# RP2040_MCU.net
KiCad netlist of a schematic drawn in Altium Designer
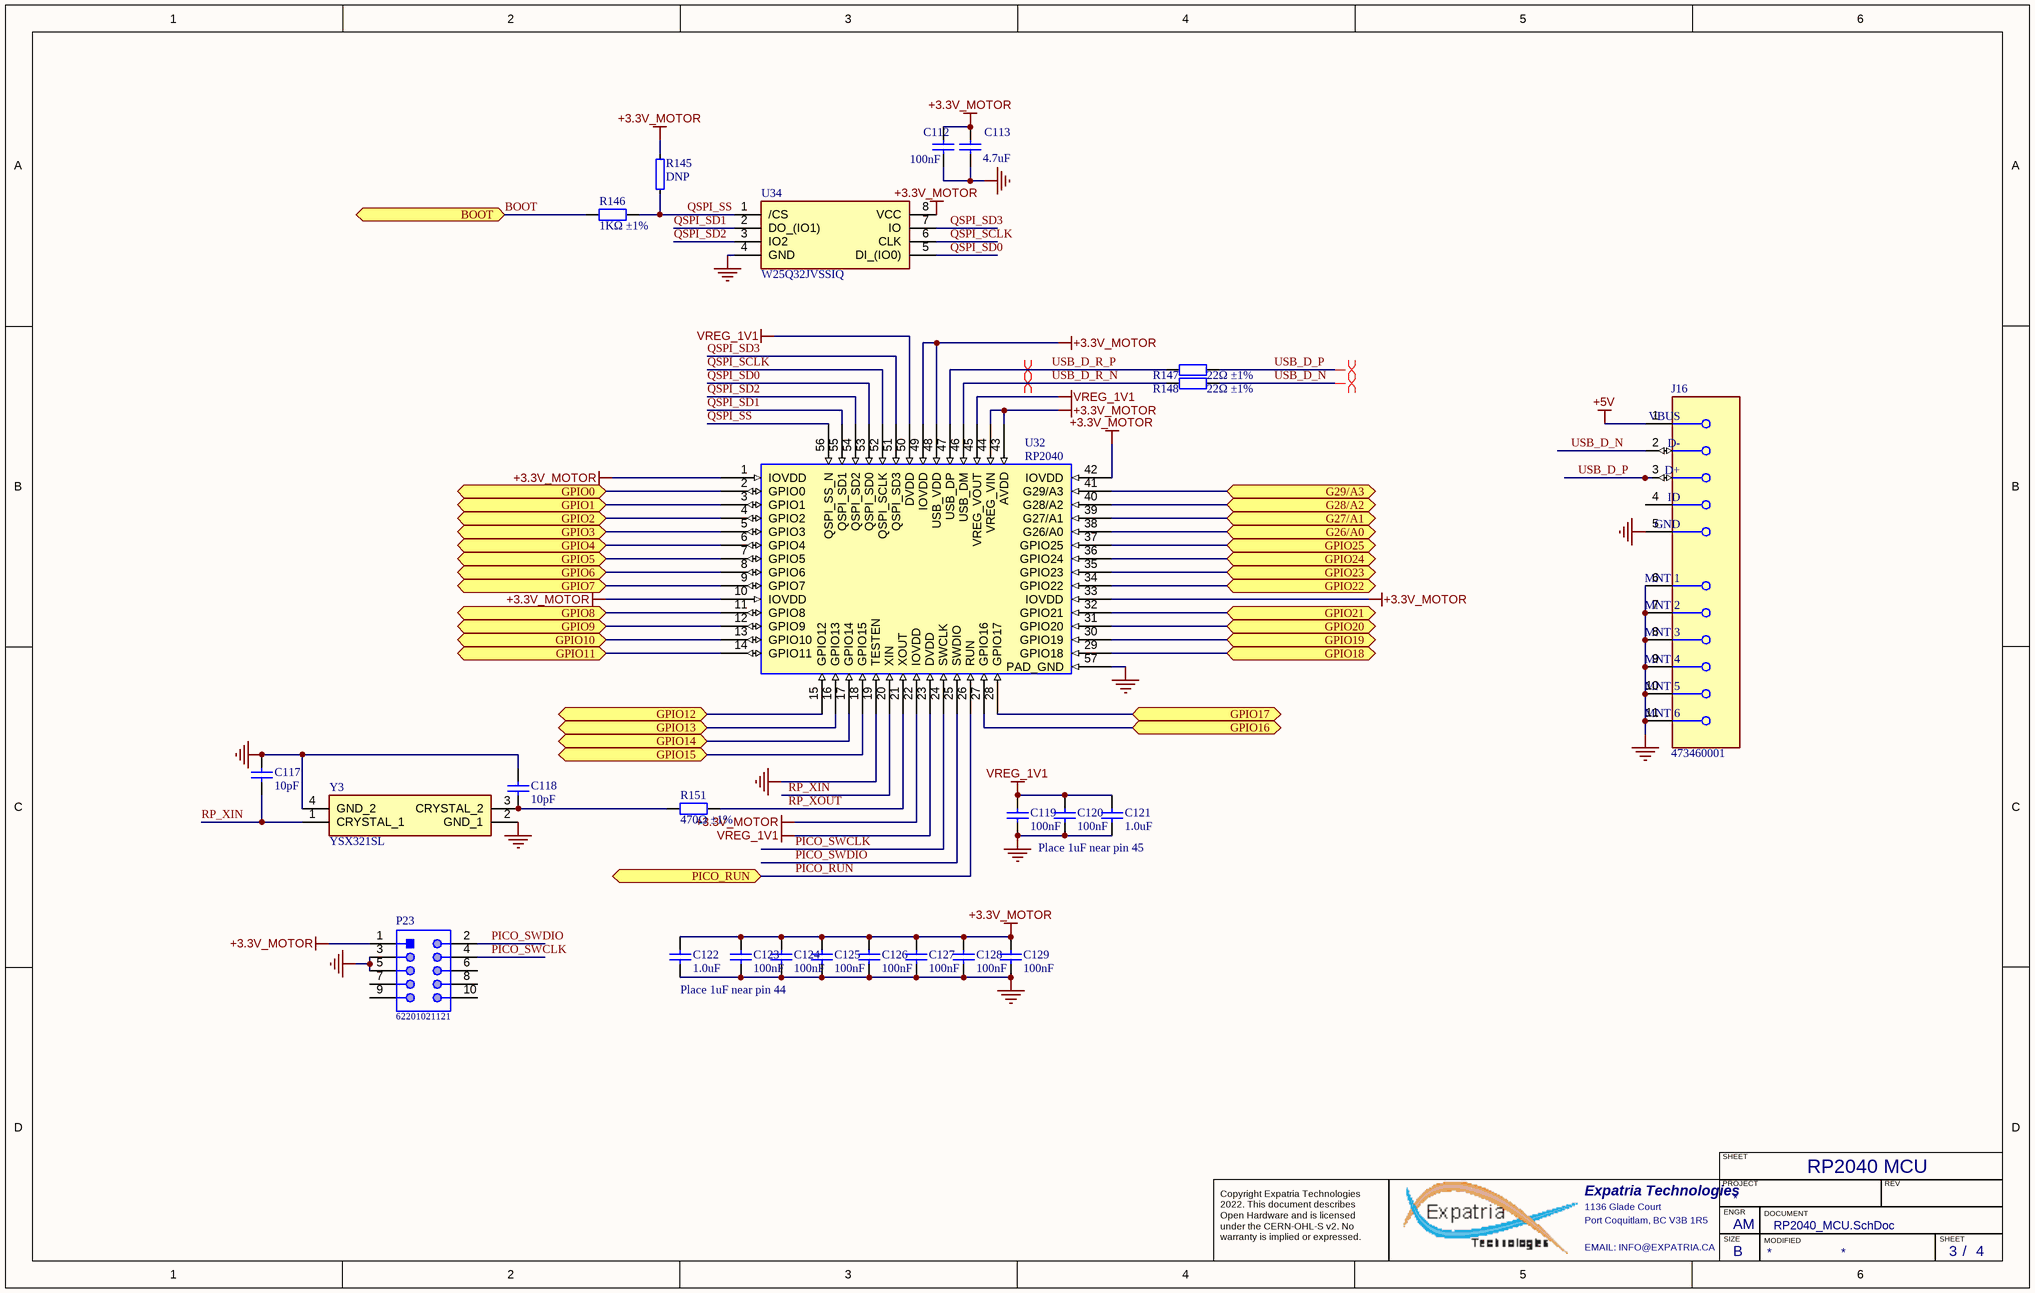
[diagram p0: RP2040_MCU.SchDoc]

(export (version "E")
  (design (tool "Eeschema 10.0.6"))
  (components
    (comp (ref "C112")
      (value "100nF")
      (footprint "0402_C")
      (description "Chip capacitors")
      (fields
        (field (name "MANUFACTURER") "Samsung Electro-Mechanics")
        (field (name "PARTNUMBER") "CL05B104KO5NNNC")
      )
      (libsource (lib "Cap") (part "0402 100nF (104) 10% 16V"))
    )
    (comp (ref "C113")
      (value "4.7uF")
      (footprint "0402_C")
      (description "Chip capacitor")
      (fields
        (field (name "MANUFACTURER") "Samsung Electro-Mechanics")
        (field (name "PARTNUMBER") "CL05A475MP5NRNC")
      )
      (libsource (lib "Cap") (part "0402 4.7uF (475) 20% 10V"))
    )
    (comp (ref "C117")
      (value "10pF")
      (footprint "0402_C")
      (description "Chip capacitors")
      (fields
        (field (name "MANUFACTURER") "Samsung Electro-Mechanics")
        (field (name "PARTNUMBER") "CL05C100JB5NNNC")
      )
      (libsource (lib "Cap") (part "0402 10pF (100) 5% 50V"))
    )
    (comp (ref "C118")
      (value "10pF")
      (footprint "0402_C")
      (description "Chip capacitors")
      (fields
        (field (name "MANUFACTURER") "Samsung Electro-Mechanics")
        (field (name "PARTNUMBER") "CL05C100JB5NNNC")
      )
      (libsource (lib "Cap") (part "0402 10pF (100) 5% 50V"))
    )
    (comp (ref "C119")
      (value "100nF")
      (footprint "0402_C")
      (description "Chip capacitors")
      (fields
        (field (name "MANUFACTURER") "Samsung Electro-Mechanics")
        (field (name "PARTNUMBER") "CL05B104KO5NNNC")
      )
      (libsource (lib "Cap") (part "0402 100nF (104) 10% 16V"))
    )
    (comp (ref "C120")
      (value "100nF")
      (footprint "0402_C")
      (description "Chip capacitors")
      (fields
        (field (name "MANUFACTURER") "Samsung Electro-Mechanics")
        (field (name "PARTNUMBER") "CL05B104KO5NNNC")
      )
      (libsource (lib "Cap") (part "0402 100nF (104) 10% 16V"))
    )
    (comp (ref "C121")
      (value "1.0uF")
      (footprint "0402_C")
      (description "Chip capacitor")
      (fields
        (field (name "MANUFACTURER") "Samsung Electro-Mechanics")
        (field (name "PARTNUMBER") "CL05A105KA5NQNC")
      )
      (libsource (lib "Cap") (part "0402 1.0uF (105) 10% 25V"))
    )
    (comp (ref "C122")
      (value "1.0uF")
      (footprint "0402_C")
      (description "Chip capacitor")
      (fields
        (field (name "MANUFACTURER") "Samsung Electro-Mechanics")
        (field (name "PARTNUMBER") "CL05A105KA5NQNC")
      )
      (libsource (lib "Cap") (part "0402 1.0uF (105) 10% 25V"))
    )
    (comp (ref "C123")
      (value "100nF")
      (footprint "0402_C")
      (description "Chip capacitors")
      (fields
        (field (name "MANUFACTURER") "Samsung Electro-Mechanics")
        (field (name "PARTNUMBER") "CL05B104KO5NNNC")
      )
      (libsource (lib "Cap") (part "0402 100nF (104) 10% 16V"))
    )
    (comp (ref "C124")
      (value "100nF")
      (footprint "0402_C")
      (description "Chip capacitors")
      (fields
        (field (name "MANUFACTURER") "Samsung Electro-Mechanics")
        (field (name "PARTNUMBER") "CL05B104KO5NNNC")
      )
      (libsource (lib "Cap") (part "0402 100nF (104) 10% 16V"))
    )
    (comp (ref "C125")
      (value "100nF")
      (footprint "0402_C")
      (description "Chip capacitors")
      (fields
        (field (name "MANUFACTURER") "Samsung Electro-Mechanics")
        (field (name "PARTNUMBER") "CL05B104KO5NNNC")
      )
      (libsource (lib "Cap") (part "0402 100nF (104) 10% 16V"))
    )
    (comp (ref "C126")
      (value "100nF")
      (footprint "0402_C")
      (description "Chip capacitors")
      (fields
        (field (name "MANUFACTURER") "Samsung Electro-Mechanics")
        (field (name "PARTNUMBER") "CL05B104KO5NNNC")
      )
      (libsource (lib "Cap") (part "0402 100nF (104) 10% 16V"))
    )
    (comp (ref "C127")
      (value "100nF")
      (footprint "0402_C")
      (description "Chip capacitors")
      (fields
        (field (name "MANUFACTURER") "Samsung Electro-Mechanics")
        (field (name "PARTNUMBER") "CL05B104KO5NNNC")
      )
      (libsource (lib "Cap") (part "0402 100nF (104) 10% 16V"))
    )
    (comp (ref "C128")
      (value "100nF")
      (footprint "0402_C")
      (description "Chip capacitors")
      (fields
        (field (name "MANUFACTURER") "Samsung Electro-Mechanics")
        (field (name "PARTNUMBER") "CL05B104KO5NNNC")
      )
      (libsource (lib "Cap") (part "0402 100nF (104) 10% 16V"))
    )
    (comp (ref "C129")
      (value "100nF")
      (footprint "0402_C")
      (description "Chip capacitors")
      (fields
        (field (name "MANUFACTURER") "Samsung Electro-Mechanics")
        (field (name "PARTNUMBER") "CL05B104KO5NNNC")
      )
      (libsource (lib "Cap") (part "0402 100nF (104) 10% 16V"))
    )
    (comp (ref "J16")
      (value "473460001")
      (footprint "FP-473460001-MFG")
      (description "CONN RCPT USB2.0 MICRO B SMD R/A")
      (fields
        (field (name "OCTOPART") "https://octopart.com/47346-0001-molex-7164928")
        (field (name "MANUFACTURER") "Molex")
      )
      (libsource (lib "Altium Content Vault") (part "53ae1f1d9b557310b43ca686e5bb76a"))
    )
    (comp (ref "P23")
      (value "62201021121")
      (footprint "62201021121")
      (description "THT Vertical Pin Header WR-PHD, Pitch 1.27 mm, Dual Row, 10 pins")
      (fields (field (name "MANUFACTURER") "Wurth Elektronik") (field (name "PUBLISHER") "WurthElektronik"))
      (libsource (lib "Altium Content Vault") (part "WE-CN-2P-M-R10"))
    )
    (comp (ref "R145")
      (value "DNP")
      (footprint "0402")
      (description "Resistor, ±5%, 0.05W")
      (fields (field (name "PART NUMBER") "R0201-0R") (field (name "PUBLISHER") "Nordic Semiconductor"))
      (libsource (lib "Passives") (part "RES"))
    )
    (comp (ref "R146")
      (value "1KΩ ±1%")
      (footprint "0402_R")
      (description "Chip resistor")
      (fields (field (name "MANUFACTURER") "Uniroyal Elec") (field (name "PARTNUMBER") "0402WGF1001TCE"))
      (libsource (lib "RES") (part "0402 1K (1001) 1%"))
    )
    (comp (ref "R147")
      (value "22Ω ±1%")
      (footprint "0402_R")
      (description "Chip resistor")
      (fields (field (name "MANUFACTURER") "Uniroyal Elec") (field (name "PARTNUMBER") "0402WGF220JTCE"))
      (libsource (lib "RES") (part "0402 22R (22R0) 1%"))
    )
    (comp (ref "R148")
      (value "22Ω ±1%")
      (footprint "0402_R")
      (description "Chip resistor")
      (fields (field (name "MANUFACTURER") "Uniroyal Elec") (field (name "PARTNUMBER") "0402WGF220JTCE"))
      (libsource (lib "RES") (part "0402 22R (22R0) 1%"))
    )
    (comp (ref "R151")
      (value "470Ω ±1%")
      (footprint "0402_R")
      (description "Chip resistor")
      (fields (field (name "MANUFACTURER") "Uniroyal Elec") (field (name "PARTNUMBER") "0402WGF4700TCE"))
      (libsource (lib "RES") (part "0402 470R (4700) 1%"))
    )
    (comp (ref "U32")
      (value "RP2040")
      (footprint "RP2040")
      (description "RP2040 First MCU from RPI")
      (libsource (lib "Universal_CNC_Breakout") (part "RP2040"))
    )
    (comp (ref "U34")
      (value "W25Q32JVSSIQ")
      (footprint "SamacSys:SOIC127P780X195-8N")
      (description "SPI Flash")
      (fields
        (field (name "MANUFACTURER_PART_NUMBER") "W25Q128JVSIQ TR")
        (field (name "MOUSER PART NUMBER") "454-W25Q128JVSIQTR")
      )
      (libsource (lib "*") (part "W25Q128JVSIQ_TR"))
    )
    (comp (ref "Y3")
      (value "YSX321SL")
      (footprint "SamacSys:YSX321SL")
      (description "Crystal or Oscillator")
      (libsource (lib "*") (part "YSX321SL"))
    )
  )
  (nets
    (net (code "1") (name "+3.3V_MOTOR") (class "Default")
      (node (ref "C112") (pin "2") (pinfunction "2_2") (pintype "passive"))
      (node (ref "C113") (pin "2") (pinfunction "2_2") (pintype "passive"))
      (node (ref "C122") (pin "2") (pinfunction "2_2") (pintype "passive"))
      (node (ref "C123") (pin "2") (pinfunction "2_2") (pintype "passive"))
      (node (ref "C124") (pin "2") (pinfunction "2_2") (pintype "passive"))
      (node (ref "C125") (pin "2") (pinfunction "2_2") (pintype "passive"))
      (node (ref "C126") (pin "2") (pinfunction "2_2") (pintype "passive"))
      (node (ref "C127") (pin "2") (pinfunction "2_2") (pintype "passive"))
      (node (ref "C128") (pin "2") (pinfunction "2_2") (pintype "passive"))
      (node (ref "C129") (pin "2") (pinfunction "2_2") (pintype "passive"))
      (node (ref "P23") (pin "1") (pinfunction "1_1") (pintype "passive"))
      (node (ref "R145") (pin "2") (pinfunction "2_2") (pintype "passive"))
      (node (ref "U32") (pin "1") (pinfunction "IOVDD_1") (pintype "input"))
      (node (ref "U32") (pin "10") (pinfunction "IOVDD_10") (pintype "input"))
      (node (ref "U32") (pin "22") (pinfunction "IOVDD_22") (pintype "input"))
      (node (ref "U32") (pin "33") (pinfunction "IOVDD_33") (pintype "input"))
      (node (ref "U32") (pin "42") (pinfunction "IOVDD_42") (pintype "input"))
      (node (ref "U32") (pin "43") (pinfunction "AVDD_43") (pintype "input"))
      (node (ref "U32") (pin "44") (pinfunction "VREG_VIN_44") (pintype "input"))
      (node (ref "U32") (pin "48") (pinfunction "USB_VDD_48") (pintype "input"))
      (node (ref "U32") (pin "49") (pinfunction "IOVDD_49") (pintype "input"))
      (node (ref "U34") (pin "8") (pinfunction "VCC_8") (pintype "passive"))
    )
    (net (code "2") (name "+5V") (class "Default")
      (node (ref "J16") (pin "1") (pinfunction "VBUS_1") (pintype "power_in"))
    )
    (net (code "3") (name "/BOOT") (class "Default")
      (node (ref "R146") (pin "1") (pinfunction "1_1") (pintype "passive"))
    )
    (net (code "4") (name "/G26{slash}A0") (class "Default")
      (node (ref "U32") (pin "38") (pinfunction "G26/A0_38") (pintype "input"))
    )
    (net (code "5") (name "/G27{slash}A1") (class "Default")
      (node (ref "U32") (pin "39") (pinfunction "G27/A1_39") (pintype "input"))
    )
    (net (code "6") (name "/G28{slash}A2") (class "Default")
      (node (ref "U32") (pin "40") (pinfunction "G28/A2_40") (pintype "input"))
    )
    (net (code "7") (name "/G29{slash}A3") (class "Default")
      (node (ref "U32") (pin "41") (pinfunction "G29/A3_41") (pintype "input"))
    )
    (net (code "8") (name "/GPIO0") (class "Default")
      (node (ref "U32") (pin "2") (pinfunction "GPIO0_2") (pintype "bidirectional"))
    )
    (net (code "9") (name "/GPIO1") (class "Default")
      (node (ref "U32") (pin "3") (pinfunction "GPIO1_3") (pintype "bidirectional"))
    )
    (net (code "10") (name "/GPIO2") (class "Default")
      (node (ref "U32") (pin "4") (pinfunction "GPIO2_4") (pintype "bidirectional"))
    )
    (net (code "11") (name "/GPIO3") (class "Default")
      (node (ref "U32") (pin "5") (pinfunction "GPIO3_5") (pintype "bidirectional"))
    )
    (net (code "12") (name "/GPIO4") (class "Default")
      (node (ref "U32") (pin "6") (pinfunction "GPIO4_6") (pintype "bidirectional"))
    )
    (net (code "13") (name "/GPIO5") (class "Default")
      (node (ref "U32") (pin "7") (pinfunction "GPIO5_7") (pintype "bidirectional"))
    )
    (net (code "14") (name "/GPIO6") (class "Default")
      (node (ref "U32") (pin "8") (pinfunction "GPIO6_8") (pintype "bidirectional"))
    )
    (net (code "15") (name "/GPIO7") (class "Default")
      (node (ref "U32") (pin "9") (pinfunction "GPIO7_9") (pintype "bidirectional"))
    )
    (net (code "16") (name "/GPIO8") (class "Default")
      (node (ref "U32") (pin "11") (pinfunction "GPIO8_11") (pintype "bidirectional"))
    )
    (net (code "17") (name "/GPIO9") (class "Default")
      (node (ref "U32") (pin "12") (pinfunction "GPIO9_12") (pintype "bidirectional"))
    )
    (net (code "18") (name "/GPIO10") (class "Default")
      (node (ref "U32") (pin "13") (pinfunction "GPIO10_13") (pintype "bidirectional"))
    )
    (net (code "19") (name "/GPIO11") (class "Default")
      (node (ref "U32") (pin "14") (pinfunction "GPIO11_14") (pintype "bidirectional"))
    )
    (net (code "20") (name "/GPIO12") (class "Default")
      (node (ref "U32") (pin "15") (pinfunction "GPIO12_15") (pintype "input"))
    )
    (net (code "21") (name "/GPIO13") (class "Default")
      (node (ref "U32") (pin "16") (pinfunction "GPIO13_16") (pintype "input"))
    )
    (net (code "22") (name "/GPIO14") (class "Default")
      (node (ref "U32") (pin "17") (pinfunction "GPIO14_17") (pintype "input"))
    )
    (net (code "23") (name "/GPIO15") (class "Default")
      (node (ref "U32") (pin "18") (pinfunction "GPIO15_18") (pintype "input"))
    )
    (net (code "24") (name "/GPIO16") (class "Default")
      (node (ref "U32") (pin "27") (pinfunction "GPIO16_27") (pintype "input"))
    )
    (net (code "25") (name "/GPIO17") (class "Default")
      (node (ref "U32") (pin "28") (pinfunction "GPIO17_28") (pintype "input"))
    )
    (net (code "26") (name "/GPIO18") (class "Default")
      (node (ref "U32") (pin "29") (pinfunction "GPIO18_29") (pintype "input"))
    )
    (net (code "27") (name "/GPIO19") (class "Default")
      (node (ref "U32") (pin "30") (pinfunction "GPIO19_30") (pintype "input"))
    )
    (net (code "28") (name "/GPIO20") (class "Default")
      (node (ref "U32") (pin "31") (pinfunction "GPIO20_31") (pintype "input"))
    )
    (net (code "29") (name "/GPIO21") (class "Default")
      (node (ref "U32") (pin "32") (pinfunction "GPIO21_32") (pintype "input"))
    )
    (net (code "30") (name "/GPIO22") (class "Default")
      (node (ref "U32") (pin "34") (pinfunction "GPIO22_34") (pintype "input"))
    )
    (net (code "31") (name "/GPIO23") (class "Default")
      (node (ref "U32") (pin "35") (pinfunction "GPIO23_35") (pintype "input"))
    )
    (net (code "32") (name "/GPIO24") (class "Default")
      (node (ref "U32") (pin "36") (pinfunction "GPIO24_36") (pintype "input"))
    )
    (net (code "33") (name "/GPIO25") (class "Default")
      (node (ref "U32") (pin "37") (pinfunction "GPIO25_37") (pintype "input"))
    )
    (net (code "34") (name "/PICO_RUN") (class "Default")
      (node (ref "U32") (pin "26") (pinfunction "RUN_26") (pintype "input"))
    )
    (net (code "35") (name "/PICO_SWCLK") (class "Default")
      (node (ref "P23") (pin "4") (pinfunction "4_4") (pintype "passive"))
      (node (ref "U32") (pin "24") (pinfunction "SWCLK_24") (pintype "input"))
    )
    (net (code "36") (name "/PICO_SWDIO") (class "Default")
      (node (ref "P23") (pin "2") (pinfunction "2_2") (pintype "passive"))
      (node (ref "U32") (pin "25") (pinfunction "SWDIO_25") (pintype "input"))
    )
    (net (code "37") (name "/QSPI_SCLK") (class "Default")
      (node (ref "U32") (pin "52") (pinfunction "QSPI_SCLK_52") (pintype "input"))
      (node (ref "U34") (pin "6") (pinfunction "CLK_6") (pintype "passive"))
    )
    (net (code "38") (name "/QSPI_SD0") (class "Default")
      (node (ref "U32") (pin "53") (pinfunction "QSPI_SD0_53") (pintype "input"))
      (node (ref "U34") (pin "5") (pinfunction "DI_(IO0)_5") (pintype "passive"))
    )
    (net (code "39") (name "/QSPI_SD1") (class "Default")
      (node (ref "U32") (pin "55") (pinfunction "QSPI_SD1_55") (pintype "input"))
      (node (ref "U34") (pin "2") (pinfunction "DO_(IO1)_2") (pintype "passive"))
    )
    (net (code "40") (name "/QSPI_SD2") (class "Default")
      (node (ref "U32") (pin "54") (pinfunction "QSPI_SD2_54") (pintype "input"))
      (node (ref "U34") (pin "3") (pinfunction "IO2_3") (pintype "passive"))
    )
    (net (code "41") (name "/QSPI_SD3") (class "Default")
      (node (ref "U32") (pin "51") (pinfunction "QSPI_SD3_51") (pintype "input"))
      (node (ref "U34") (pin "7") (pinfunction "IO_7") (pintype "passive"))
    )
    (net (code "42") (name "/QSPI_SS") (class "Default")
      (node (ref "R145") (pin "1") (pinfunction "1_1") (pintype "passive"))
      (node (ref "R146") (pin "2") (pinfunction "2_2") (pintype "passive"))
      (node (ref "U32") (pin "56") (pinfunction "QSPI_SS_N_56") (pintype "input"))
      (node (ref "U34") (pin "1") (pinfunction "/CS_1") (pintype "passive"))
    )
    (net (code "43") (name "/RP_XIN") (class "Default")
      (node (ref "C117") (pin "1") (pinfunction "1_1") (pintype "passive"))
      (node (ref "U32") (pin "20") (pinfunction "XIN_20") (pintype "input"))
      (node (ref "Y3") (pin "1") (pinfunction "CRYSTAL_1_1") (pintype "passive"))
    )
    (net (code "44") (name "/RP_XOUT") (class "Default")
      (node (ref "R151") (pin "2") (pinfunction "2_2") (pintype "passive"))
      (node (ref "U32") (pin "21") (pinfunction "XOUT_21") (pintype "input"))
    )
    (net (code "45") (name "/USB_D_N") (class "Default")
      (node (ref "J16") (pin "2") (pinfunction "D-_2") (pintype "bidirectional"))
      (node (ref "R148") (pin "1") (pinfunction "1_1") (pintype "passive"))
    )
    (net (code "46") (name "/USB_D_P") (class "Default")
      (node (ref "J16") (pin "3") (pinfunction "D+_3") (pintype "bidirectional"))
      (node (ref "R147") (pin "1") (pinfunction "1_1") (pintype "passive"))
    )
    (net (code "47") (name "/USB_D_R_N") (class "Default")
      (node (ref "R148") (pin "2") (pinfunction "2_2") (pintype "passive"))
      (node (ref "U32") (pin "46") (pinfunction "USB_DM_46") (pintype "input"))
    )
    (net (code "48") (name "/USB_D_R_P") (class "Default")
      (node (ref "R147") (pin "2") (pinfunction "2_2") (pintype "passive"))
      (node (ref "U32") (pin "47") (pinfunction "USB_DP_47") (pintype "input"))
    )
    (net (code "49") (name "GND") (class "Default")
      (node (ref "C112") (pin "1") (pinfunction "1_1") (pintype "passive"))
      (node (ref "C113") (pin "1") (pinfunction "1_1") (pintype "passive"))
      (node (ref "C117") (pin "2") (pinfunction "2_2") (pintype "passive"))
      (node (ref "C118") (pin "2") (pinfunction "2_2") (pintype "passive"))
      (node (ref "C119") (pin "1") (pinfunction "1_1") (pintype "passive"))
      (node (ref "C120") (pin "1") (pinfunction "1_1") (pintype "passive"))
      (node (ref "C121") (pin "1") (pinfunction "1_1") (pintype "passive"))
      (node (ref "C122") (pin "1") (pinfunction "1_1") (pintype "passive"))
      (node (ref "C123") (pin "1") (pinfunction "1_1") (pintype "passive"))
      (node (ref "C124") (pin "1") (pinfunction "1_1") (pintype "passive"))
      (node (ref "C125") (pin "1") (pinfunction "1_1") (pintype "passive"))
      (node (ref "C126") (pin "1") (pinfunction "1_1") (pintype "passive"))
      (node (ref "C127") (pin "1") (pinfunction "1_1") (pintype "passive"))
      (node (ref "C128") (pin "1") (pinfunction "1_1") (pintype "passive"))
      (node (ref "C129") (pin "1") (pinfunction "1_1") (pintype "passive"))
      (node (ref "J16") (pin "10") (pinfunction "MNT_5_10") (pintype "passive"))
      (node (ref "J16") (pin "11") (pinfunction "MNT_6_11") (pintype "passive"))
      (node (ref "J16") (pin "5") (pinfunction "GND_5") (pintype "power_in"))
      (node (ref "J16") (pin "6") (pinfunction "MNT_1_6") (pintype "passive"))
      (node (ref "J16") (pin "7") (pinfunction "MNT_2_7") (pintype "passive"))
      (node (ref "J16") (pin "8") (pinfunction "MNT_3_8") (pintype "passive"))
      (node (ref "J16") (pin "9") (pinfunction "MNT_4_9") (pintype "passive"))
      (node (ref "P23") (pin "3") (pinfunction "3_3") (pintype "passive"))
      (node (ref "P23") (pin "5") (pinfunction "5_5") (pintype "passive"))
      (node (ref "U32") (pin "19") (pinfunction "TESTEN_19") (pintype "input"))
      (node (ref "U32") (pin "57") (pinfunction "PAD_GND_57") (pintype "input"))
      (node (ref "U34") (pin "4") (pinfunction "GND_4") (pintype "passive"))
      (node (ref "Y3") (pin "2") (pinfunction "GND_1_2") (pintype "passive"))
      (node (ref "Y3") (pin "4") (pinfunction "GND_2_4") (pintype "passive"))
    )
    (net (code "50") (name "Net-(Y3-CRYSTAL_2)") (class "Default")
      (node (ref "C118") (pin "1") (pinfunction "1_1") (pintype "passive"))
      (node (ref "R151") (pin "1") (pinfunction "1_1") (pintype "passive"))
      (node (ref "Y3") (pin "3") (pinfunction "CRYSTAL_2_3") (pintype "passive"))
    )
    (net (code "51") (name "VREG_1V1") (class "Default")
      (node (ref "C119") (pin "2") (pinfunction "2_2") (pintype "passive"))
      (node (ref "C120") (pin "2") (pinfunction "2_2") (pintype "passive"))
      (node (ref "C121") (pin "2") (pinfunction "2_2") (pintype "passive"))
      (node (ref "U32") (pin "23") (pinfunction "DVDD_23") (pintype "input"))
      (node (ref "U32") (pin "45") (pinfunction "VREG_VOUT_45") (pintype "input"))
      (node (ref "U32") (pin "50") (pinfunction "DVDD_50") (pintype "input"))
    )
    (net (code "52") (name "unconnected-(J16-ID-Pad4)") (class "Default")
      (node (ref "J16") (pin "4") (pinfunction "ID_4") (pintype "passive"))
    )
    (net (code "53") (name "unconnected-(P23-Pad6)") (class "Default")
      (node (ref "P23") (pin "6") (pinfunction "6_6") (pintype "passive"))
    )
    (net (code "54") (name "unconnected-(P23-Pad7)") (class "Default")
      (node (ref "P23") (pin "7") (pinfunction "7_7") (pintype "passive"))
    )
    (net (code "55") (name "unconnected-(P23-Pad8)") (class "Default")
      (node (ref "P23") (pin "8") (pinfunction "8_8") (pintype "passive"))
    )
    (net (code "56") (name "unconnected-(P23-Pad9)") (class "Default")
      (node (ref "P23") (pin "9") (pinfunction "9_9") (pintype "passive"))
    )
    (net (code "57") (name "unconnected-(P23-Pad10)") (class "Default")
      (node (ref "P23") (pin "10") (pinfunction "10_10") (pintype "passive"))
    )
  )
)
